# LedBricksPlate2x6.net
KiCad netlist of a schematic drawn in EAGLE
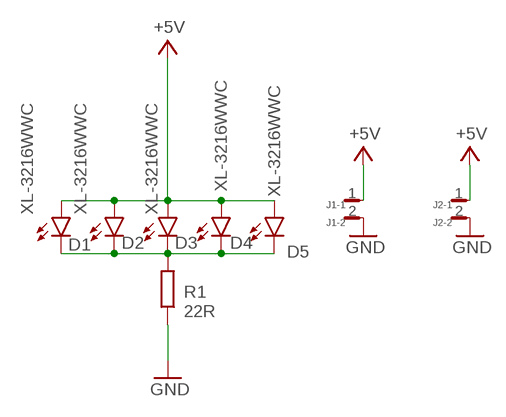
[diagram p0: schematic, sheet 1]

(export (version "E")
  (design (tool "Eeschema 10.0.6"))
  (components
    (comp (ref "D1")
      (value "XL-3216WWC")
      (footprint "eagle-import:LED-1206")
      (libsource (lib "eagle-import") (part "LED1206"))
    )
    (comp (ref "D2")
      (value "XL-3216WWC")
      (footprint "eagle-import:LED-1206")
      (libsource (lib "eagle-import") (part "LED1206"))
    )
    (comp (ref "D3")
      (value "XL-3216WWC")
      (footprint "eagle-import:LED-1206")
      (libsource (lib "eagle-import") (part "LED1206"))
    )
    (comp (ref "D4")
      (value "XL-3216WWC")
      (footprint "eagle-import:LED-1206")
      (libsource (lib "eagle-import") (part "LED1206"))
    )
    (comp (ref "D5")
      (value "XL-3216WWC")
      (footprint "eagle-import:LED-1206")
      (libsource (lib "eagle-import") (part "LED1206"))
    )
    (comp (ref "J1")
      (value "SM02B-SRSS-TB")
      (footprint "eagle-import:SM02B-SRSS-TB")
      (fields (field (name "MF") "JST"))
      (libsource (lib "eagle-import") (part "SM02B-SRSS-TB"))
    )
    (comp (ref "J2")
      (value "SM02B-SRSS-TB")
      (footprint "eagle-import:SM02B-SRSS-TB")
      (fields (field (name "MF") "JST"))
      (libsource (lib "eagle-import") (part "SM02B-SRSS-TB"))
    )
    (comp (ref "R1")
      (value "22R")
      (footprint "eagle-import:R0805")
      (libsource (lib "eagle-import") (part "R-EU_R0805"))
    )
  )
  (nets
    (net (code "1") (name "+5V") (class "Default")
      (node (ref "D1") (pin "A") (pinfunction "A_A") (pintype "passive"))
      (node (ref "D2") (pin "A") (pinfunction "A_A") (pintype "passive"))
      (node (ref "D3") (pin "A") (pinfunction "A_A") (pintype "passive"))
      (node (ref "D4") (pin "A") (pinfunction "A_A") (pintype "passive"))
      (node (ref "D5") (pin "A") (pinfunction "A_A") (pintype "passive"))
      (node (ref "J1") (pin "1") (pinfunction "P_1") (pintype "bidirectional"))
      (node (ref "J2") (pin "1") (pinfunction "P_1") (pintype "bidirectional"))
    )
    (net (code "2") (name "GND") (class "Default")
      (node (ref "J1") (pin "2") (pinfunction "P_2") (pintype "bidirectional"))
      (node (ref "J2") (pin "2") (pinfunction "P_2") (pintype "bidirectional"))
      (node (ref "R1") (pin "1") (pinfunction "1_1") (pintype "passive"))
    )
    (net (code "3") (name "Net-(D1-PadC)") (class "Default")
      (node (ref "D1") (pin "C") (pinfunction "C_C") (pintype "passive"))
      (node (ref "D2") (pin "C") (pinfunction "C_C") (pintype "passive"))
      (node (ref "D3") (pin "C") (pinfunction "C_C") (pintype "passive"))
      (node (ref "D4") (pin "C") (pinfunction "C_C") (pintype "passive"))
      (node (ref "D5") (pin "C") (pinfunction "C_C") (pintype "passive"))
      (node (ref "R1") (pin "2") (pinfunction "2_2") (pintype "passive"))
    )
  )
)
